# Clock_module.net
KiCad netlist of a schematic drawn in Altium Designer
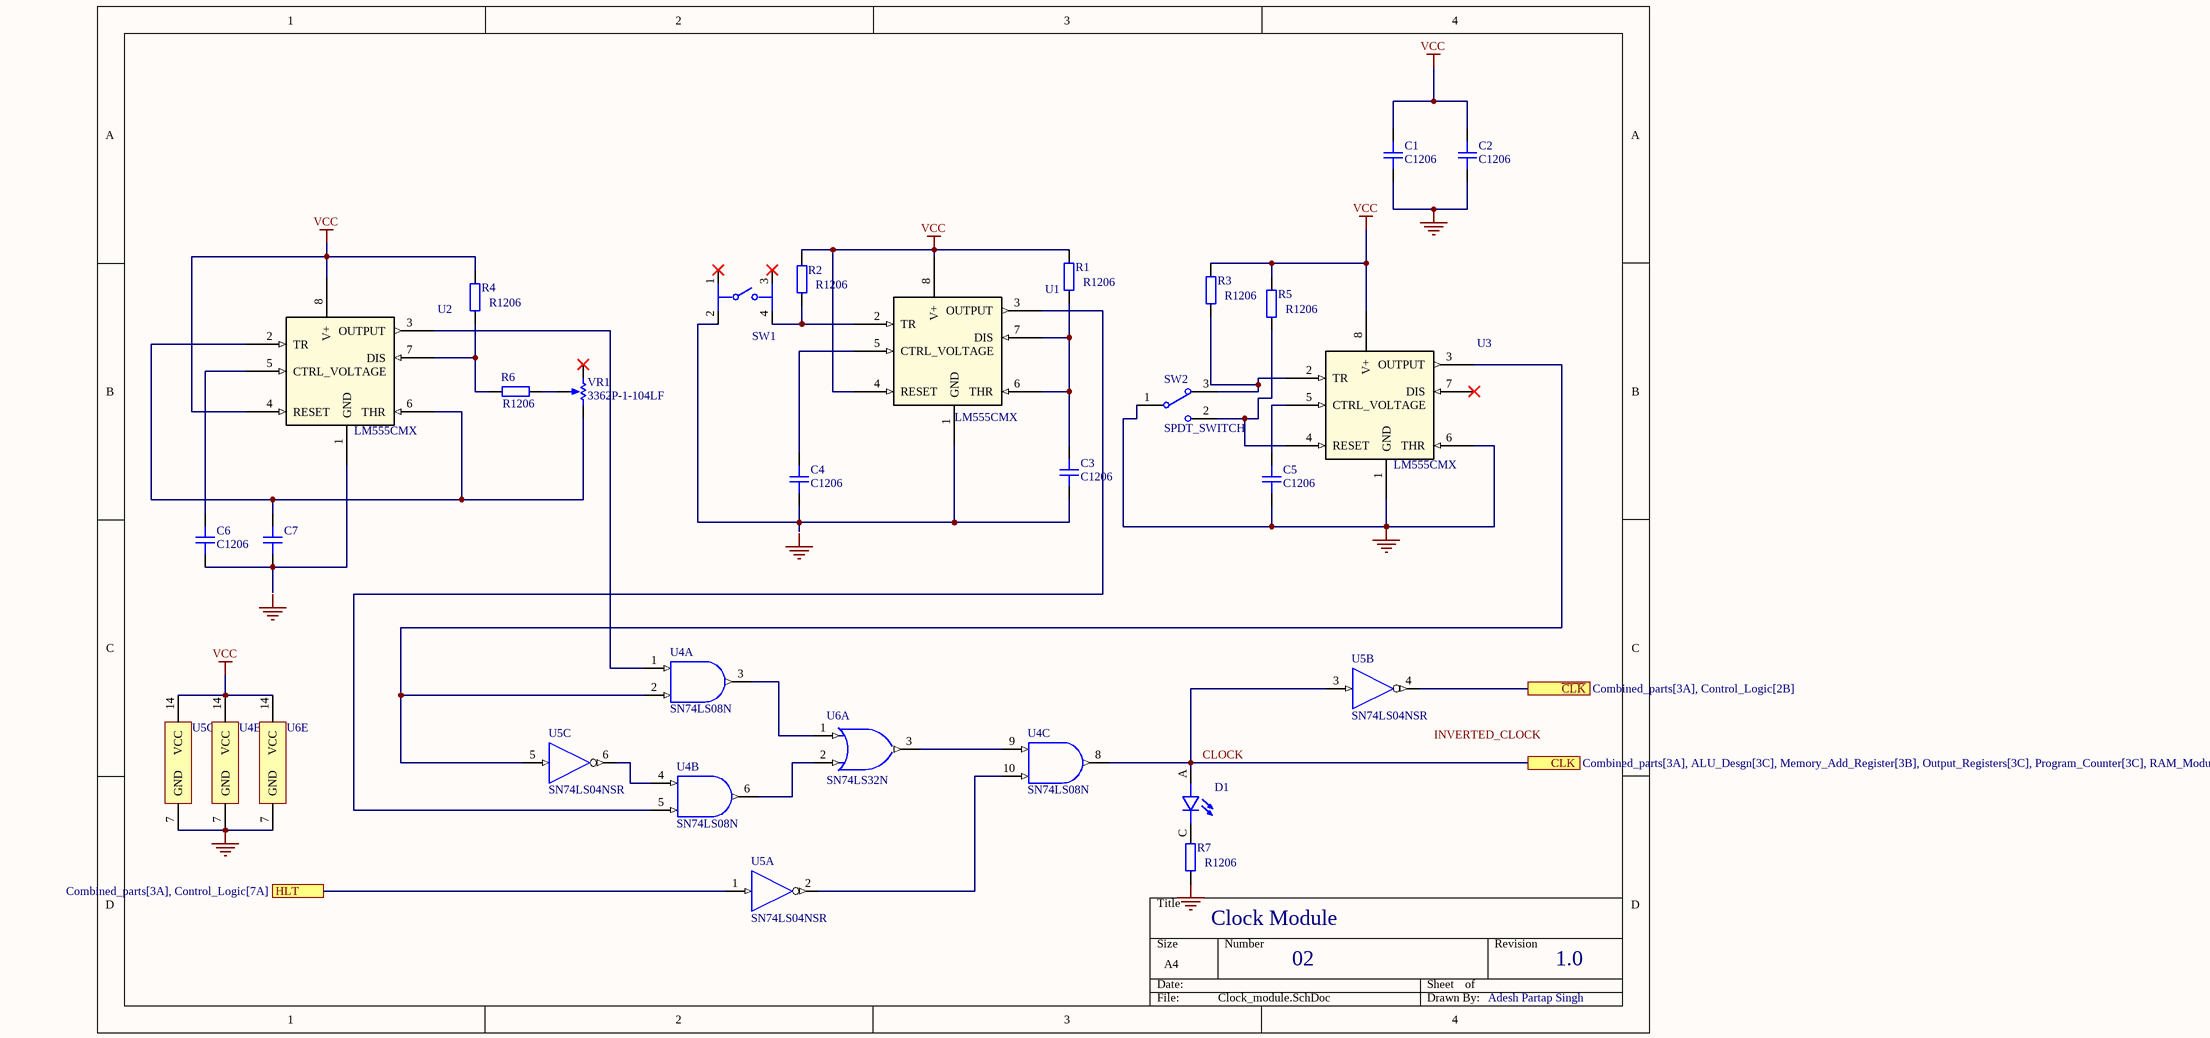
[diagram p0: Clock_module.SchDoc]

(export (version "E")
  (design (tool "Eeschema 10.0.6"))
  (components
    (comp (ref "C1")
      (value "C1206")
      (footprint "CAP_1206")
      (description "Capacitor SMD 1206")
      (libsource (lib "Schematic-Lib-PhilsLab") (part "CAP_1206"))
    )
    (comp (ref "C2")
      (value "C1206")
      (footprint "CAP_1206")
      (description "Capacitor SMD 1206")
      (libsource (lib "Schematic-Lib-PhilsLab") (part "CAP_1206"))
    )
    (comp (ref "C3")
      (value "C1206")
      (footprint "CAP_1206")
      (description "Capacitor SMD 1206")
      (libsource (lib "Schematic-Lib-PhilsLab") (part "CAP_1206"))
    )
    (comp (ref "C4")
      (value "C1206")
      (footprint "CAP_1206")
      (description "Capacitor SMD 1206")
      (libsource (lib "Schematic-Lib-PhilsLab") (part "CAP_1206"))
    )
    (comp (ref "C5")
      (value "C1206")
      (footprint "CAP_1206")
      (description "Capacitor SMD 1206")
      (libsource (lib "Schematic-Lib-PhilsLab") (part "CAP_1206"))
    )
    (comp (ref "C6")
      (value "C1206")
      (footprint "CAP_1206")
      (description "Capacitor SMD 1206")
      (libsource (lib "Schematic-Lib-PhilsLab") (part "CAP_1206"))
    )
    (comp (ref "C7")
      (value "CAP_EL_NP_5MM")
      (footprint "CAP-EL-NP-5MM")
      (description "Capacitor SMD Electrolytic Non-Polarised 5mm Diameter")
      (fields (field (name "MANUFACTURER") "Nichicon"))
      (libsource (lib "Schematic-Lib-PhilsLab") (part "CAP_EL_NP_5MM"))
    )
    (comp (ref "D1")
      (value "L08R5000Q1")
      (footprint "LEDRD254W57D500H1070")
      (fields (field (name "MF") "LED Technology"))
      (libsource (lib "8BIT_COMP_LIB") (part "L08R5000Q1"))
    )
    (comp (ref "R1")
      (value "R1206")
      (footprint "RES_1206")
      (description "Resistor SMD 1206")
      (libsource (lib "Schematic-Lib-PhilsLab") (part "RES_1206"))
    )
    (comp (ref "R2")
      (value "R1206")
      (footprint "RES_1206")
      (description "Resistor SMD 1206")
      (libsource (lib "Schematic-Lib-PhilsLab") (part "RES_1206"))
    )
    (comp (ref "R3")
      (value "R1206")
      (footprint "RES_1206")
      (description "Resistor SMD 1206")
      (libsource (lib "Schematic-Lib-PhilsLab") (part "RES_1206"))
    )
    (comp (ref "R4")
      (value "R1206")
      (footprint "RES_1206")
      (description "Resistor SMD 1206")
      (libsource (lib "Schematic-Lib-PhilsLab") (part "RES_1206"))
    )
    (comp (ref "R5")
      (value "R1206")
      (footprint "RES_1206")
      (description "Resistor SMD 1206")
      (libsource (lib "Schematic-Lib-PhilsLab") (part "RES_1206"))
    )
    (comp (ref "R6")
      (value "R1206")
      (footprint "RES_1206")
      (description "Resistor SMD 1206")
      (libsource (lib "Schematic-Lib-PhilsLab") (part "RES_1206"))
    )
    (comp (ref "R7")
      (value "R1206")
      (footprint "RES_1206")
      (description "Resistor SMD 1206")
      (libsource (lib "Schematic-Lib-PhilsLab") (part "RES_1206"))
    )
    (comp (ref "SW1")
      (value "3-1825910-1")
      (footprint "FP-3-1825910-1-MFG")
      (description "SWITCH TACTILE SPST-NO 0.05A 24V")
      (fields
        (field (name "MANUFACTURER") "TE Connectivity")
        (field (name "OCTOPART") "https://octopart.com/3-1825910-1-te+connectivity-46506874")
      )
      (libsource (lib "Altium Content Vault") (part "b8895f3f4cefb76e1819d2863dba89b"))
    )
    (comp (ref "SW2")
      (value "SPDT_SWITCH")
      (footprint "EOZ-09.03201.02-3")
      (libsource (lib "8BIT_COMP_LIB") (part "SWITCH_SPDT"))
    )
    (comp (ref "U1")
      (value "LM555CMX")
      (footprint "SOIC-8_ONS")
      (description "No Description Available")
      (fields (field (name "COPYRIGHT") "Copyright (C) 2023 Ultra Librarian. All rights reserved."))
      (libsource (lib "8BIT_COMP_LIB") (part "LM555CMX"))
    )
    (comp (ref "U2")
      (value "LM555CMX")
      (footprint "SOIC-8_ONS")
      (description "No Description Available")
      (fields (field (name "COPYRIGHT") "Copyright (C) 2023 Ultra Librarian. All rights reserved."))
      (libsource (lib "8BIT_COMP_LIB") (part "LM555CMX"))
    )
    (comp (ref "U3")
      (value "LM555CMX")
      (footprint "SOIC-8_ONS")
      (description "No Description Available")
      (fields (field (name "COPYRIGHT") "Copyright (C) 2023 Ultra Librarian. All rights reserved."))
      (libsource (lib "8BIT_COMP_LIB") (part "LM555CMX"))
    )
    (comp (ref "U4")
      (value "SN74LS08N")
      (footprint "N0014A")
      (description "Quadruple 2-Input Positive-AND Gates, N0014A, TUBE")
      (fields
        (field (name "MANUFACTURER") "Texas Instruments")
        (field (name "GENERIC PART NUMBER") "SN74LS08")
      )
      (libsource (lib "8BIT_COMP_LIB") (part "CMP-0777-00259-3"))
    )
    (comp (ref "U5")
      (value "SN74LS04NSR")
      (footprint "NS0014A_M")
      (description "Hex inverters, NS0014A, LARGE T&R")
      (fields
        (field (name "MANUFACTURER") "Texas Instruments")
        (field (name "GENERIC PART NUMBER") "SN74LS04")
      )
      (libsource (lib "8BIT_COMP_LIB") (part "CMP-1615-00958-3"))
    )
    (comp (ref "U6")
      (value "SN74LS32N")
      (footprint "OR_GATE_PCB")
      (description "Quad 2-input positive-OR gates, N0014A, TUBE")
      (fields
        (field (name "GENERIC PART NUMBER") "SN74LS32")
        (field (name "MANUFACTURER") "Texas Instruments")
      )
      (libsource (lib "") (part "CMP-1573-00145-3_1_1"))
    )
    (comp (ref "VR1")
      (value "3362P-1-104LF")
      (footprint "BOUR-3362P")
      (description "Square Trimpot(R) Trimming Potentiometer, 100 KOhm, 300 V, -55 to 125 degC, 3-Pin THD, RoHS, Tube")
      (fields (field (name "TOLERANCE") "1%"))
      (libsource (lib "Altium Content Vault") (part "RES-POT-3"))
    )
  )
  (nets
    (net (code "1") (name "/CLOCK") (class "Default")
      (node (ref "D1") (pin "A") (pinfunction "A_A") (pintype "passive"))
      (node (ref "U4") (pin "8") (pinfunction "3Y_8") (pintype "output"))
      (node (ref "U5") (pin "3") (pinfunction "2A_3") (pintype "input"))
    )
    (net (code "2") (name "/HLT") (class "Default")
      (node (ref "U5") (pin "1") (pinfunction "1A_1") (pintype "input"))
    )
    (net (code "4") (name "/~{CLK}") (class "Default")
      (node (ref "U5") (pin "4") (pinfunction "~{2Y}_4") (pintype "output"))
    )
    (net (code "5") (name "GND") (class "Default")
      (node (ref "C1") (pin "1") (pinfunction "1_1") (pintype "passive"))
      (node (ref "C2") (pin "1") (pinfunction "1_1") (pintype "passive"))
      (node (ref "C5") (pin "1") (pinfunction "1_1") (pintype "passive"))
      (node (ref "R7") (pin "1") (pinfunction "1_1") (pintype "passive"))
      (node (ref "SW2") (pin "1") (pinfunction "1_1") (pintype "passive"))
      (node (ref "U3") (pin "1") (pinfunction "GND_1") (pintype "power_in"))
      (node (ref "U3") (pin "6") (pinfunction "THR_6") (pintype "input"))
      (node (ref "U4") (pin "7") (pinfunction "GND_7") (pintype "power_in"))
      (node (ref "U5") (pin "7") (pinfunction "GND_7") (pintype "power_in"))
      (node (ref "U6") (pin "7") (pinfunction "GND_7") (pintype "power_in"))
    )
    (net (code "6") (name "Net-(U1-CTRL_VOLTAGE)") (class "Default")
      (node (ref "C4") (pin "2") (pinfunction "2_2") (pintype "passive"))
      (node (ref "U1") (pin "5") (pinfunction "CTRL_VOLTAGE_5") (pintype "input"))
    )
    (net (code "7") (name "Net-(U1-DIS)") (class "Default")
      (node (ref "C3") (pin "2") (pinfunction "2_2") (pintype "passive"))
      (node (ref "R1") (pin "1") (pinfunction "1_1") (pintype "passive"))
      (node (ref "U1") (pin "6") (pinfunction "THR_6") (pintype "input"))
      (node (ref "U1") (pin "7") (pinfunction "DIS_7") (pintype "input"))
    )
    (net (code "8") (name "Net-(U1-GND)") (class "Default")
      (node (ref "C3") (pin "1") (pinfunction "1_1") (pintype "passive"))
      (node (ref "C4") (pin "1") (pinfunction "1_1") (pintype "passive"))
      (node (ref "SW1") (pin "2") (pinfunction "2_2") (pintype "passive"))
      (node (ref "U1") (pin "1") (pinfunction "GND_1") (pintype "power_in"))
    )
    (net (code "9") (name "Net-(U1-OUTPUT)") (class "Default")
      (node (ref "U1") (pin "3") (pinfunction "OUTPUT_3") (pintype "output"))
      (node (ref "U4") (pin "5") (pinfunction "2B_5") (pintype "input"))
    )
    (net (code "10") (name "Net-(U1-TR)") (class "Default")
      (node (ref "R2") (pin "1") (pinfunction "1_1") (pintype "passive"))
      (node (ref "SW1") (pin "4") (pinfunction "4_4") (pintype "passive"))
      (node (ref "U1") (pin "2") (pinfunction "TR_2") (pintype "input"))
    )
    (net (code "11") (name "Net-(U2-CTRL_VOLTAGE)") (class "Default")
      (node (ref "C6") (pin "2") (pinfunction "2_2") (pintype "passive"))
      (node (ref "U2") (pin "5") (pinfunction "CTRL_VOLTAGE_5") (pintype "input"))
    )
    (net (code "12") (name "Net-(U2-DIS)") (class "Default")
      (node (ref "R4") (pin "1") (pinfunction "1_1") (pintype "passive"))
      (node (ref "R6") (pin "1") (pinfunction "1_1") (pintype "passive"))
      (node (ref "U2") (pin "7") (pinfunction "DIS_7") (pintype "input"))
    )
    (net (code "13") (name "Net-(U2-GND)") (class "Default")
      (node (ref "C6") (pin "1") (pinfunction "1_1") (pintype "passive"))
      (node (ref "C7") (pin "1") (pinfunction "1_1") (pintype "passive"))
      (node (ref "U2") (pin "1") (pinfunction "GND_1") (pintype "power_in"))
    )
    (net (code "14") (name "Net-(U2-OUTPUT)") (class "Default")
      (node (ref "U2") (pin "3") (pinfunction "OUTPUT_3") (pintype "output"))
      (node (ref "U4") (pin "1") (pinfunction "1A_1") (pintype "input"))
    )
    (net (code "15") (name "Net-(U2-THR)") (class "Default")
      (node (ref "C7") (pin "2") (pinfunction "2_2") (pintype "passive"))
      (node (ref "U2") (pin "2") (pinfunction "TR_2") (pintype "input"))
      (node (ref "U2") (pin "6") (pinfunction "THR_6") (pintype "input"))
      (node (ref "VR1") (pin "3") (pinfunction "CW_3") (pintype "passive"))
    )
    (net (code "16") (name "Net-(U3-CTRL_VOLTAGE)") (class "Default")
      (node (ref "C5") (pin "2") (pinfunction "2_2") (pintype "passive"))
      (node (ref "U3") (pin "5") (pinfunction "CTRL_VOLTAGE_5") (pintype "input"))
    )
    (net (code "17") (name "Net-(U3-OUTPUT)") (class "Default")
      (node (ref "U3") (pin "3") (pinfunction "OUTPUT_3") (pintype "output"))
      (node (ref "U4") (pin "2") (pinfunction "1B_2") (pintype "input"))
      (node (ref "U5") (pin "5") (pinfunction "3A_5") (pintype "input"))
    )
    (net (code "18") (name "Net-(U3-RESET)") (class "Default")
      (node (ref "R5") (pin "1") (pinfunction "1_1") (pintype "passive"))
      (node (ref "SW2") (pin "2") (pinfunction "2_2") (pintype "passive"))
      (node (ref "U3") (pin "4") (pinfunction "RESET_4") (pintype "input"))
    )
    (net (code "19") (name "Net-(U3-TR)") (class "Default")
      (node (ref "R3") (pin "1") (pinfunction "1_1") (pintype "passive"))
      (node (ref "SW2") (pin "3") (pinfunction "3_3") (pintype "passive"))
      (node (ref "U3") (pin "2") (pinfunction "TR_2") (pintype "input"))
    )
    (net (code "20") (name "Net-(U4A-1Y)") (class "Default")
      (node (ref "U4") (pin "3") (pinfunction "1Y_3") (pintype "output"))
      (node (ref "U6") (pin "1") (pinfunction "1A_1") (pintype "input"))
    )
    (net (code "21") (name "Net-(U4B-2A)") (class "Default")
      (node (ref "U4") (pin "4") (pinfunction "2A_4") (pintype "input"))
      (node (ref "U5") (pin "6") (pinfunction "~{3Y}_6") (pintype "output"))
    )
    (net (code "22") (name "Net-(U4B-2Y)") (class "Default")
      (node (ref "U4") (pin "6") (pinfunction "2Y_6") (pintype "output"))
      (node (ref "U6") (pin "2") (pinfunction "1B_2") (pintype "input"))
    )
    (net (code "23") (name "Net-(U4C-3A)") (class "Default")
      (node (ref "U4") (pin "9") (pinfunction "3A_9") (pintype "input"))
      (node (ref "U6") (pin "3") (pinfunction "1Y_3") (pintype "output"))
    )
    (net (code "24") (name "Net-(U4C-3B)") (class "Default")
      (node (ref "U4") (pin "10") (pinfunction "3B_10") (pintype "input"))
      (node (ref "U5") (pin "2") (pinfunction "~{1Y}_2") (pintype "output"))
    )
    (net (code "25") (name "Net-(VR1-S)") (class "Default")
      (node (ref "R6") (pin "2") (pinfunction "2_2") (pintype "passive"))
      (node (ref "VR1") (pin "2") (pinfunction "S_2") (pintype "passive"))
    )
    (net (code "26") (name "VCC") (class "Default")
      (node (ref "C1") (pin "2") (pinfunction "2_2") (pintype "passive"))
      (node (ref "C2") (pin "2") (pinfunction "2_2") (pintype "passive"))
      (node (ref "R1") (pin "2") (pinfunction "2_2") (pintype "passive"))
      (node (ref "R2") (pin "2") (pinfunction "2_2") (pintype "passive"))
      (node (ref "R3") (pin "2") (pinfunction "2_2") (pintype "passive"))
      (node (ref "R4") (pin "2") (pinfunction "2_2") (pintype "passive"))
      (node (ref "R5") (pin "2") (pinfunction "2_2") (pintype "passive"))
      (node (ref "U1") (pin "4") (pinfunction "RESET_4") (pintype "input"))
      (node (ref "U1") (pin "8") (pinfunction "V+_8") (pintype "power_in"))
      (node (ref "U2") (pin "4") (pinfunction "RESET_4") (pintype "input"))
      (node (ref "U2") (pin "8") (pinfunction "V+_8") (pintype "power_in"))
      (node (ref "U3") (pin "8") (pinfunction "V+_8") (pintype "power_in"))
      (node (ref "U4") (pin "14") (pinfunction "VCC_14") (pintype "power_in"))
      (node (ref "U5") (pin "14") (pinfunction "VCC_14") (pintype "power_in"))
      (node (ref "U6") (pin "14") (pinfunction "VCC_14") (pintype "power_in"))
    )
    (net (code "27") (name "unconnected-(D1-PadC)") (class "Default")
      (node (ref "D1") (pin "C") (pinfunction "C_C") (pintype "passive"))
    )
    (net (code "28") (name "unconnected-(R7-Pad2)") (class "Default")
      (node (ref "R7") (pin "2") (pinfunction "2_2") (pintype "passive"))
    )
    (net (code "29") (name "unconnected-(SW1-Pad1)") (class "Default")
      (node (ref "SW1") (pin "1") (pinfunction "1_1") (pintype "passive+no_connect"))
    )
    (net (code "30") (name "unconnected-(SW1-Pad3)") (class "Default")
      (node (ref "SW1") (pin "3") (pinfunction "3_3") (pintype "passive+no_connect"))
    )
    (net (code "31") (name "unconnected-(U3-DIS-Pad7)") (class "Default")
      (node (ref "U3") (pin "7") (pinfunction "DIS_7") (pintype "input+no_connect"))
    )
    (net (code "32") (name "unconnected-(VR1-CCW-Pad1)") (class "Default")
      (node (ref "VR1") (pin "1") (pinfunction "CCW_1") (pintype "passive+no_connect"))
    )
  )
)
